# DR_EIB-128_Circle_0_25MM.net
KiCad netlist of a schematic drawn in EAGLE
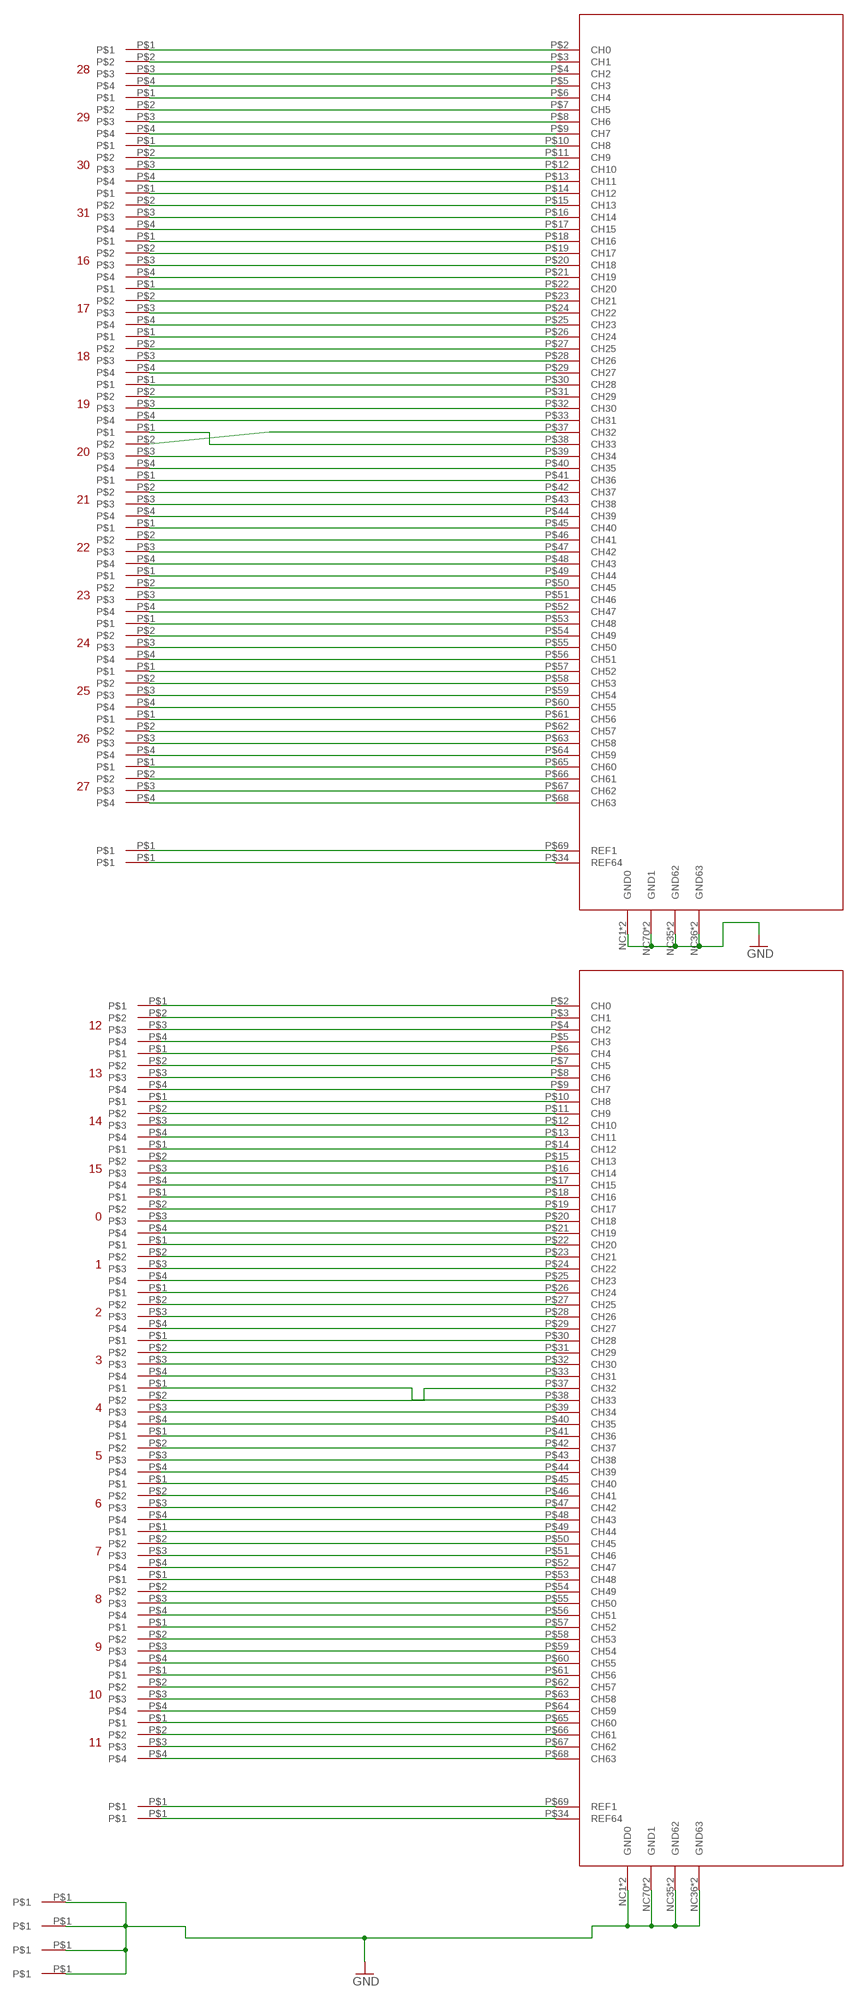
[diagram p0: schematic, sheet 1]

(export (version "E")
  (design (tool "Eeschema 10.0.6"))
  (components
    (comp (ref "0")
      (value "TETRODE_1.5IN_RADIUS0.25MM")
      (footprint "eagle-import:TETRODE_1.5IN_RADIUS_0.25MM")
      (libsource (lib "eagle-import") (part "TETRODE_1.5IN_RADIUS0.25MM"))
    )
    (comp (ref "1")
      (value "TETRODE_1.5IN_RADIUS0.25MM")
      (footprint "eagle-import:TETRODE_1.5IN_RADIUS_0.25MM")
      (libsource (lib "eagle-import") (part "TETRODE_1.5IN_RADIUS0.25MM"))
    )
    (comp (ref "2")
      (value "TETRODE_1.5IN_RADIUS0.25MM")
      (footprint "eagle-import:TETRODE_1.5IN_RADIUS_0.25MM")
      (libsource (lib "eagle-import") (part "TETRODE_1.5IN_RADIUS0.25MM"))
    )
    (comp (ref "3")
      (value "TETRODE_1.5IN_RADIUS0.25MM")
      (footprint "eagle-import:TETRODE_1.5IN_RADIUS_0.25MM")
      (libsource (lib "eagle-import") (part "TETRODE_1.5IN_RADIUS0.25MM"))
    )
    (comp (ref "4")
      (value "TETRODE_1.5IN_RADIUS0.25MM")
      (footprint "eagle-import:TETRODE_1.5IN_RADIUS_0.25MM")
      (libsource (lib "eagle-import") (part "TETRODE_1.5IN_RADIUS0.25MM"))
    )
    (comp (ref "5")
      (value "TETRODE_1.5IN_RADIUS0.25MM")
      (footprint "eagle-import:TETRODE_1.5IN_RADIUS_0.25MM")
      (libsource (lib "eagle-import") (part "TETRODE_1.5IN_RADIUS0.25MM"))
    )
    (comp (ref "6")
      (value "TETRODE_1.5IN_RADIUS0.25MM")
      (footprint "eagle-import:TETRODE_1.5IN_RADIUS_0.25MM")
      (libsource (lib "eagle-import") (part "TETRODE_1.5IN_RADIUS0.25MM"))
    )
    (comp (ref "7")
      (value "TETRODE_1.5IN_RADIUS0.25MM")
      (footprint "eagle-import:TETRODE_1.5IN_RADIUS_0.25MM")
      (libsource (lib "eagle-import") (part "TETRODE_1.5IN_RADIUS0.25MM"))
    )
    (comp (ref "8")
      (value "TETRODE_1.5IN_RADIUS0.25MM")
      (footprint "eagle-import:TETRODE_1.5IN_RADIUS_0.25MM")
      (libsource (lib "eagle-import") (part "TETRODE_1.5IN_RADIUS0.25MM"))
    )
    (comp (ref "9")
      (value "TETRODE_1.5IN_RADIUS0.25MM")
      (footprint "eagle-import:TETRODE_1.5IN_RADIUS_0.25MM")
      (libsource (lib "eagle-import") (part "TETRODE_1.5IN_RADIUS0.25MM"))
    )
    (comp (ref "10")
      (value "TETRODE_1.5IN_RADIUS0.25MM")
      (footprint "eagle-import:TETRODE_1.5IN_RADIUS_0.25MM")
      (libsource (lib "eagle-import") (part "TETRODE_1.5IN_RADIUS0.25MM"))
    )
    (comp (ref "11")
      (value "TETRODE_1.5IN_RADIUS0.25MM")
      (footprint "eagle-import:TETRODE_1.5IN_RADIUS_0.25MM")
      (libsource (lib "eagle-import") (part "TETRODE_1.5IN_RADIUS0.25MM"))
    )
    (comp (ref "12")
      (value "TETRODE_1.5IN_RADIUS0.25MM")
      (footprint "eagle-import:TETRODE_1.5IN_RADIUS_0.25MM")
      (libsource (lib "eagle-import") (part "TETRODE_1.5IN_RADIUS0.25MM"))
    )
    (comp (ref "13")
      (value "TETRODE_1.5IN_RADIUS0.25MM")
      (footprint "eagle-import:TETRODE_1.5IN_RADIUS_0.25MM")
      (libsource (lib "eagle-import") (part "TETRODE_1.5IN_RADIUS0.25MM"))
    )
    (comp (ref "14")
      (value "TETRODE_1.5IN_RADIUS0.25MM")
      (footprint "eagle-import:TETRODE_1.5IN_RADIUS_0.25MM")
      (libsource (lib "eagle-import") (part "TETRODE_1.5IN_RADIUS0.25MM"))
    )
    (comp (ref "15")
      (value "TETRODE_1.5IN_RADIUS0.25MM")
      (footprint "eagle-import:TETRODE_1.5IN_RADIUS_0.25MM")
      (libsource (lib "eagle-import") (part "TETRODE_1.5IN_RADIUS0.25MM"))
    )
    (comp (ref "16")
      (value "TETRODE_1.5IN_RADIUS0.25MM")
      (footprint "eagle-import:TETRODE_1.5IN_RADIUS_0.25MM")
      (libsource (lib "eagle-import") (part "TETRODE_1.5IN_RADIUS0.25MM"))
    )
    (comp (ref "17")
      (value "TETRODE_1.5IN_RADIUS0.25MM")
      (footprint "eagle-import:TETRODE_1.5IN_RADIUS_0.25MM")
      (libsource (lib "eagle-import") (part "TETRODE_1.5IN_RADIUS0.25MM"))
    )
    (comp (ref "18")
      (value "TETRODE_1.5IN_RADIUS0.25MM")
      (footprint "eagle-import:TETRODE_1.5IN_RADIUS_0.25MM")
      (libsource (lib "eagle-import") (part "TETRODE_1.5IN_RADIUS0.25MM"))
    )
    (comp (ref "19")
      (value "TETRODE_1.5IN_RADIUS0.25MM")
      (footprint "eagle-import:TETRODE_1.5IN_RADIUS_0.25MM")
      (libsource (lib "eagle-import") (part "TETRODE_1.5IN_RADIUS0.25MM"))
    )
    (comp (ref "20")
      (value "TETRODE_1.5IN_RADIUS0.25MM")
      (footprint "eagle-import:TETRODE_1.5IN_RADIUS_0.25MM")
      (libsource (lib "eagle-import") (part "TETRODE_1.5IN_RADIUS0.25MM"))
    )
    (comp (ref "21")
      (value "TETRODE_1.5IN_RADIUS0.25MM")
      (footprint "eagle-import:TETRODE_1.5IN_RADIUS_0.25MM")
      (libsource (lib "eagle-import") (part "TETRODE_1.5IN_RADIUS0.25MM"))
    )
    (comp (ref "22")
      (value "TETRODE_1.5IN_RADIUS0.25MM")
      (footprint "eagle-import:TETRODE_1.5IN_RADIUS_0.25MM")
      (libsource (lib "eagle-import") (part "TETRODE_1.5IN_RADIUS0.25MM"))
    )
    (comp (ref "23")
      (value "TETRODE_1.5IN_RADIUS0.25MM")
      (footprint "eagle-import:TETRODE_1.5IN_RADIUS_0.25MM")
      (libsource (lib "eagle-import") (part "TETRODE_1.5IN_RADIUS0.25MM"))
    )
    (comp (ref "24")
      (value "TETRODE_1.5IN_RADIUS0.25MM")
      (footprint "eagle-import:TETRODE_1.5IN_RADIUS_0.25MM")
      (libsource (lib "eagle-import") (part "TETRODE_1.5IN_RADIUS0.25MM"))
    )
    (comp (ref "25")
      (value "TETRODE_1.5IN_RADIUS0.25MM")
      (footprint "eagle-import:TETRODE_1.5IN_RADIUS_0.25MM")
      (libsource (lib "eagle-import") (part "TETRODE_1.5IN_RADIUS0.25MM"))
    )
    (comp (ref "26")
      (value "TETRODE_1.5IN_RADIUS0.25MM")
      (footprint "eagle-import:TETRODE_1.5IN_RADIUS_0.25MM")
      (libsource (lib "eagle-import") (part "TETRODE_1.5IN_RADIUS0.25MM"))
    )
    (comp (ref "27")
      (value "TETRODE_1.5IN_RADIUS0.25MM")
      (footprint "eagle-import:TETRODE_1.5IN_RADIUS_0.25MM")
      (libsource (lib "eagle-import") (part "TETRODE_1.5IN_RADIUS0.25MM"))
    )
    (comp (ref "28")
      (value "TETRODE_1.5IN_RADIUS0.25MM")
      (footprint "eagle-import:TETRODE_1.5IN_RADIUS_0.25MM")
      (libsource (lib "eagle-import") (part "TETRODE_1.5IN_RADIUS0.25MM"))
    )
    (comp (ref "29")
      (value "TETRODE_1.5IN_RADIUS0.25MM")
      (footprint "eagle-import:TETRODE_1.5IN_RADIUS_0.25MM")
      (libsource (lib "eagle-import") (part "TETRODE_1.5IN_RADIUS0.25MM"))
    )
    (comp (ref "30")
      (value "TETRODE_1.5IN_RADIUS0.25MM")
      (footprint "eagle-import:TETRODE_1.5IN_RADIUS_0.25MM")
      (libsource (lib "eagle-import") (part "TETRODE_1.5IN_RADIUS0.25MM"))
    )
    (comp (ref "31")
      (value "TETRODE_1.5IN_RADIUS0.25MM")
      (footprint "eagle-import:TETRODE_1.5IN_RADIUS_0.25MM")
      (libsource (lib "eagle-import") (part "TETRODE_1.5IN_RADIUS0.25MM"))
    )
    (comp (ref "U$1")
      (value "TARRAYSHUTTLEHOLE")
      (footprint "eagle-import:TARRAYSHUTTLEHOLE")
      (libsource (lib "eagle-import") (part "TARRAYSHUTTLEHOLE"))
    )
    (comp (ref "U$2")
      (value "TARRAYSHUTTLEHOLE")
      (footprint "eagle-import:TARRAYSHUTTLEHOLE")
      (libsource (lib "eagle-import") (part "TARRAYSHUTTLEHOLE"))
    )
    (comp (ref "U$4")
      (value "TARRAYSHUTTLEHOLE")
      (footprint "eagle-import:TARRAYSHUTTLEHOLE")
      (libsource (lib "eagle-import") (part "TARRAYSHUTTLEHOLE"))
    )
    (comp (ref "U$5")
      (value "TARRAYSHUTTLEHOLE")
      (footprint "eagle-import:TARRAYSHUTTLEHOLE")
      (libsource (lib "eagle-import") (part "TARRAYSHUTTLEHOLE"))
    )
    (comp (ref "U$6")
      (value "TARRAYSHUTTLEHOLE")
      (footprint "eagle-import:TARRAYSHUTTLEHOLE")
      (libsource (lib "eagle-import") (part "TARRAYSHUTTLEHOLE"))
    )
    (comp (ref "U$7")
      (value "TARRAYSHUTTLEHOLE")
      (footprint "eagle-import:TARRAYSHUTTLEHOLE")
      (libsource (lib "eagle-import") (part "TARRAYSHUTTLEHOLE"))
    )
    (comp (ref "U$8")
      (value "TARRAYSHUTTLEHOLE")
      (footprint "eagle-import:TARRAYSHUTTLEHOLE")
      (libsource (lib "eagle-import") (part "TARRAYSHUTTLEHOLE"))
    )
    (comp (ref "U$9")
      (value "TARRAYSHUTTLEHOLE")
      (footprint "eagle-import:TARRAYSHUTTLEHOLE")
      (libsource (lib "eagle-import") (part "TARRAYSHUTTLEHOLE"))
    )
    (comp (ref "U$10")
      (value "HIROSE-70PIN-HEADER-SEQUENTIAL")
      (footprint "eagle-import:DF40C-70DP-0.4V")
      (libsource (lib "eagle-import") (part "HIROSE-70PIN-HEADER-SEQUENTIAL"))
    )
    (comp (ref "U$11")
      (value "HIROSE-70PIN-HEADER-SEQUENTIAL")
      (footprint "eagle-import:DF40C-70DP-0.4V")
      (libsource (lib "eagle-import") (part "HIROSE-70PIN-HEADER-SEQUENTIAL"))
    )
  )
  (nets
    (net (code "1") (name "GND") (class "Default")
      (node (ref "U$1") (pin "P$1") (pinfunction "P$1_P$1") (pintype "bidirectional"))
      (node (ref "U$10") (pin "NC1") (pinfunction "GND0_NC1") (pintype "power_in"))
      (node (ref "U$10") (pin "NC35") (pinfunction "GND62_NC35") (pintype "power_in"))
      (node (ref "U$10") (pin "NC36") (pinfunction "GND63_NC36") (pintype "power_in"))
      (node (ref "U$10") (pin "NC70") (pinfunction "GND1_NC70") (pintype "power_in"))
      (node (ref "U$10") (pin "P$1") (pinfunction "GND0_P$1") (pintype "power_in"))
      (node (ref "U$10") (pin "P$35") (pinfunction "GND62_P$35") (pintype "power_in"))
      (node (ref "U$10") (pin "P$36") (pinfunction "GND63_P$36") (pintype "power_in"))
      (node (ref "U$10") (pin "P$70") (pinfunction "GND1_P$70") (pintype "power_in"))
      (node (ref "U$11") (pin "NC1") (pinfunction "GND0_NC1") (pintype "power_in"))
      (node (ref "U$11") (pin "NC35") (pinfunction "GND62_NC35") (pintype "power_in"))
      (node (ref "U$11") (pin "NC36") (pinfunction "GND63_NC36") (pintype "power_in"))
      (node (ref "U$11") (pin "NC70") (pinfunction "GND1_NC70") (pintype "power_in"))
      (node (ref "U$11") (pin "P$1") (pinfunction "GND0_P$1") (pintype "power_in"))
      (node (ref "U$11") (pin "P$35") (pinfunction "GND62_P$35") (pintype "power_in"))
      (node (ref "U$11") (pin "P$36") (pinfunction "GND63_P$36") (pintype "power_in"))
      (node (ref "U$11") (pin "P$70") (pinfunction "GND1_P$70") (pintype "power_in"))
      (node (ref "U$2") (pin "P$1") (pinfunction "P$1_P$1") (pintype "bidirectional"))
      (node (ref "U$4") (pin "P$1") (pinfunction "P$1_P$1") (pintype "bidirectional"))
      (node (ref "U$5") (pin "P$1") (pinfunction "P$1_P$1") (pintype "bidirectional"))
    )
    (net (code "2") (name "Net-(U$10-CH0)") (class "Default")
      (node (ref "28") (pin "P$1") (pinfunction "P$1_P$1") (pintype "bidirectional"))
      (node (ref "U$10") (pin "P$2") (pinfunction "CH0_P$2") (pintype "input"))
    )
    (net (code "3") (name "Net-(U$10-CH1)") (class "Default")
      (node (ref "28") (pin "P$2") (pinfunction "P$2_P$2") (pintype "bidirectional"))
      (node (ref "U$10") (pin "P$3") (pinfunction "CH1_P$3") (pintype "input"))
    )
    (net (code "4") (name "Net-(U$10-CH2)") (class "Default")
      (node (ref "28") (pin "P$3") (pinfunction "P$3_P$3") (pintype "bidirectional"))
      (node (ref "U$10") (pin "P$4") (pinfunction "CH2_P$4") (pintype "input"))
    )
    (net (code "5") (name "Net-(U$10-CH3)") (class "Default")
      (node (ref "28") (pin "P$4") (pinfunction "P$4_P$4") (pintype "bidirectional"))
      (node (ref "U$10") (pin "P$5") (pinfunction "CH3_P$5") (pintype "input"))
    )
    (net (code "6") (name "Net-(U$10-CH4)") (class "Default")
      (node (ref "29") (pin "P$1") (pinfunction "P$1_P$1") (pintype "bidirectional"))
      (node (ref "U$10") (pin "P$6") (pinfunction "CH4_P$6") (pintype "input"))
    )
    (net (code "7") (name "Net-(U$10-CH5)") (class "Default")
      (node (ref "29") (pin "P$2") (pinfunction "P$2_P$2") (pintype "bidirectional"))
      (node (ref "U$10") (pin "P$7") (pinfunction "CH5_P$7") (pintype "input"))
    )
    (net (code "8") (name "Net-(U$10-CH6)") (class "Default")
      (node (ref "29") (pin "P$3") (pinfunction "P$3_P$3") (pintype "bidirectional"))
      (node (ref "U$10") (pin "P$8") (pinfunction "CH6_P$8") (pintype "input"))
    )
    (net (code "9") (name "Net-(U$10-CH7)") (class "Default")
      (node (ref "29") (pin "P$4") (pinfunction "P$4_P$4") (pintype "bidirectional"))
      (node (ref "U$10") (pin "P$9") (pinfunction "CH7_P$9") (pintype "input"))
    )
    (net (code "10") (name "Net-(U$10-CH8)") (class "Default")
      (node (ref "30") (pin "P$1") (pinfunction "P$1_P$1") (pintype "bidirectional"))
      (node (ref "U$10") (pin "P$10") (pinfunction "CH8_P$10") (pintype "input"))
    )
    (net (code "11") (name "Net-(U$10-CH9)") (class "Default")
      (node (ref "30") (pin "P$2") (pinfunction "P$2_P$2") (pintype "bidirectional"))
      (node (ref "U$10") (pin "P$11") (pinfunction "CH9_P$11") (pintype "input"))
    )
    (net (code "12") (name "Net-(U$10-CH10)") (class "Default")
      (node (ref "30") (pin "P$3") (pinfunction "P$3_P$3") (pintype "bidirectional"))
      (node (ref "U$10") (pin "P$12") (pinfunction "CH10_P$12") (pintype "input"))
    )
    (net (code "13") (name "Net-(U$10-CH11)") (class "Default")
      (node (ref "30") (pin "P$4") (pinfunction "P$4_P$4") (pintype "bidirectional"))
      (node (ref "U$10") (pin "P$13") (pinfunction "CH11_P$13") (pintype "input"))
    )
    (net (code "14") (name "Net-(U$10-CH12)") (class "Default")
      (node (ref "31") (pin "P$1") (pinfunction "P$1_P$1") (pintype "bidirectional"))
      (node (ref "U$10") (pin "P$14") (pinfunction "CH12_P$14") (pintype "input"))
    )
    (net (code "15") (name "Net-(U$10-CH13)") (class "Default")
      (node (ref "31") (pin "P$2") (pinfunction "P$2_P$2") (pintype "bidirectional"))
      (node (ref "U$10") (pin "P$15") (pinfunction "CH13_P$15") (pintype "input"))
    )
    (net (code "16") (name "Net-(U$10-CH14)") (class "Default")
      (node (ref "31") (pin "P$3") (pinfunction "P$3_P$3") (pintype "bidirectional"))
      (node (ref "U$10") (pin "P$16") (pinfunction "CH14_P$16") (pintype "input"))
    )
    (net (code "17") (name "Net-(U$10-CH15)") (class "Default")
      (node (ref "31") (pin "P$4") (pinfunction "P$4_P$4") (pintype "bidirectional"))
      (node (ref "U$10") (pin "P$17") (pinfunction "CH15_P$17") (pintype "input"))
    )
    (net (code "18") (name "Net-(U$10-CH16)") (class "Default")
      (node (ref "16") (pin "P$1") (pinfunction "P$1_P$1") (pintype "bidirectional"))
      (node (ref "U$10") (pin "P$18") (pinfunction "CH16_P$18") (pintype "input"))
    )
    (net (code "19") (name "Net-(U$10-CH17)") (class "Default")
      (node (ref "16") (pin "P$2") (pinfunction "P$2_P$2") (pintype "bidirectional"))
      (node (ref "U$10") (pin "P$19") (pinfunction "CH17_P$19") (pintype "input"))
    )
    (net (code "20") (name "Net-(U$10-CH18)") (class "Default")
      (node (ref "16") (pin "P$3") (pinfunction "P$3_P$3") (pintype "bidirectional"))
      (node (ref "U$10") (pin "P$20") (pinfunction "CH18_P$20") (pintype "input"))
    )
    (net (code "21") (name "Net-(U$10-CH19)") (class "Default")
      (node (ref "16") (pin "P$4") (pinfunction "P$4_P$4") (pintype "bidirectional"))
      (node (ref "U$10") (pin "P$21") (pinfunction "CH19_P$21") (pintype "input"))
    )
    (net (code "22") (name "Net-(U$10-CH20)") (class "Default")
      (node (ref "17") (pin "P$1") (pinfunction "P$1_P$1") (pintype "bidirectional"))
      (node (ref "U$10") (pin "P$22") (pinfunction "CH20_P$22") (pintype "input"))
    )
    (net (code "23") (name "Net-(U$10-CH21)") (class "Default")
      (node (ref "17") (pin "P$2") (pinfunction "P$2_P$2") (pintype "bidirectional"))
      (node (ref "U$10") (pin "P$23") (pinfunction "CH21_P$23") (pintype "input"))
    )
    (net (code "24") (name "Net-(U$10-CH22)") (class "Default")
      (node (ref "17") (pin "P$3") (pinfunction "P$3_P$3") (pintype "bidirectional"))
      (node (ref "U$10") (pin "P$24") (pinfunction "CH22_P$24") (pintype "input"))
    )
    (net (code "25") (name "Net-(U$10-CH23)") (class "Default")
      (node (ref "17") (pin "P$4") (pinfunction "P$4_P$4") (pintype "bidirectional"))
      (node (ref "U$10") (pin "P$25") (pinfunction "CH23_P$25") (pintype "input"))
    )
    (net (code "26") (name "Net-(U$10-CH24)") (class "Default")
      (node (ref "18") (pin "P$1") (pinfunction "P$1_P$1") (pintype "bidirectional"))
      (node (ref "U$10") (pin "P$26") (pinfunction "CH24_P$26") (pintype "input"))
    )
    (net (code "27") (name "Net-(U$10-CH25)") (class "Default")
      (node (ref "18") (pin "P$2") (pinfunction "P$2_P$2") (pintype "bidirectional"))
      (node (ref "U$10") (pin "P$27") (pinfunction "CH25_P$27") (pintype "input"))
    )
    (net (code "28") (name "Net-(U$10-CH26)") (class "Default")
      (node (ref "18") (pin "P$3") (pinfunction "P$3_P$3") (pintype "bidirectional"))
      (node (ref "U$10") (pin "P$28") (pinfunction "CH26_P$28") (pintype "input"))
    )
    (net (code "29") (name "Net-(U$10-CH27)") (class "Default")
      (node (ref "18") (pin "P$4") (pinfunction "P$4_P$4") (pintype "bidirectional"))
      (node (ref "U$10") (pin "P$29") (pinfunction "CH27_P$29") (pintype "input"))
    )
    (net (code "30") (name "Net-(U$10-CH28)") (class "Default")
      (node (ref "19") (pin "P$1") (pinfunction "P$1_P$1") (pintype "bidirectional"))
      (node (ref "U$10") (pin "P$30") (pinfunction "CH28_P$30") (pintype "input"))
    )
    (net (code "31") (name "Net-(U$10-CH29)") (class "Default")
      (node (ref "19") (pin "P$2") (pinfunction "P$2_P$2") (pintype "bidirectional"))
      (node (ref "U$10") (pin "P$31") (pinfunction "CH29_P$31") (pintype "input"))
    )
    (net (code "32") (name "Net-(U$10-CH30)") (class "Default")
      (node (ref "19") (pin "P$3") (pinfunction "P$3_P$3") (pintype "bidirectional"))
      (node (ref "U$10") (pin "P$32") (pinfunction "CH30_P$32") (pintype "input"))
    )
    (net (code "33") (name "Net-(U$10-CH31)") (class "Default")
      (node (ref "19") (pin "P$4") (pinfunction "P$4_P$4") (pintype "bidirectional"))
      (node (ref "U$10") (pin "P$33") (pinfunction "CH31_P$33") (pintype "input"))
    )
    (net (code "34") (name "Net-(U$10-CH32)") (class "Default")
      (node (ref "20") (pin "P$2") (pinfunction "P$2_P$2") (pintype "bidirectional"))
      (node (ref "U$10") (pin "P$37") (pinfunction "CH32_P$37") (pintype "input"))
    )
    (net (code "35") (name "Net-(U$10-CH33)") (class "Default")
      (node (ref "20") (pin "P$1") (pinfunction "P$1_P$1") (pintype "bidirectional"))
      (node (ref "U$10") (pin "P$38") (pinfunction "CH33_P$38") (pintype "input"))
    )
    (net (code "36") (name "Net-(U$10-CH34)") (class "Default")
      (node (ref "20") (pin "P$3") (pinfunction "P$3_P$3") (pintype "bidirectional"))
      (node (ref "U$10") (pin "P$39") (pinfunction "CH34_P$39") (pintype "input"))
    )
    (net (code "37") (name "Net-(U$10-CH35)") (class "Default")
      (node (ref "20") (pin "P$4") (pinfunction "P$4_P$4") (pintype "bidirectional"))
      (node (ref "U$10") (pin "P$40") (pinfunction "CH35_P$40") (pintype "input"))
    )
    (net (code "38") (name "Net-(U$10-CH36)") (class "Default")
      (node (ref "21") (pin "P$1") (pinfunction "P$1_P$1") (pintype "bidirectional"))
      (node (ref "U$10") (pin "P$41") (pinfunction "CH36_P$41") (pintype "input"))
    )
    (net (code "39") (name "Net-(U$10-CH37)") (class "Default")
      (node (ref "21") (pin "P$2") (pinfunction "P$2_P$2") (pintype "bidirectional"))
      (node (ref "U$10") (pin "P$42") (pinfunction "CH37_P$42") (pintype "input"))
    )
    (net (code "40") (name "Net-(U$10-CH38)") (class "Default")
      (node (ref "21") (pin "P$3") (pinfunction "P$3_P$3") (pintype "bidirectional"))
      (node (ref "U$10") (pin "P$43") (pinfunction "CH38_P$43") (pintype "input"))
    )
    (net (code "41") (name "Net-(U$10-CH39)") (class "Default")
      (node (ref "21") (pin "P$4") (pinfunction "P$4_P$4") (pintype "bidirectional"))
      (node (ref "U$10") (pin "P$44") (pinfunction "CH39_P$44") (pintype "input"))
    )
    (net (code "42") (name "Net-(U$10-CH40)") (class "Default")
      (node (ref "22") (pin "P$1") (pinfunction "P$1_P$1") (pintype "bidirectional"))
      (node (ref "U$10") (pin "P$45") (pinfunction "CH40_P$45") (pintype "input"))
    )
    (net (code "43") (name "Net-(U$10-CH41)") (class "Default")
      (node (ref "22") (pin "P$2") (pinfunction "P$2_P$2") (pintype "bidirectional"))
      (node (ref "U$10") (pin "P$46") (pinfunction "CH41_P$46") (pintype "input"))
    )
    (net (code "44") (name "Net-(U$10-CH42)") (class "Default")
      (node (ref "22") (pin "P$3") (pinfunction "P$3_P$3") (pintype "bidirectional"))
      (node (ref "U$10") (pin "P$47") (pinfunction "CH42_P$47") (pintype "input"))
    )
    (net (code "45") (name "Net-(U$10-CH43)") (class "Default")
      (node (ref "22") (pin "P$4") (pinfunction "P$4_P$4") (pintype "bidirectional"))
      (node (ref "U$10") (pin "P$48") (pinfunction "CH43_P$48") (pintype "input"))
    )
    (net (code "46") (name "Net-(U$10-CH44)") (class "Default")
      (node (ref "23") (pin "P$1") (pinfunction "P$1_P$1") (pintype "bidirectional"))
      (node (ref "U$10") (pin "P$49") (pinfunction "CH44_P$49") (pintype "input"))
    )
    (net (code "47") (name "Net-(U$10-CH45)") (class "Default")
      (node (ref "23") (pin "P$2") (pinfunction "P$2_P$2") (pintype "bidirectional"))
      (node (ref "U$10") (pin "P$50") (pinfunction "CH45_P$50") (pintype "input"))
    )
    (net (code "48") (name "Net-(U$10-CH46)") (class "Default")
      (node (ref "23") (pin "P$3") (pinfunction "P$3_P$3") (pintype "bidirectional"))
      (node (ref "U$10") (pin "P$51") (pinfunction "CH46_P$51") (pintype "input"))
    )
    (net (code "49") (name "Net-(U$10-CH47)") (class "Default")
      (node (ref "23") (pin "P$4") (pinfunction "P$4_P$4") (pintype "bidirectional"))
      (node (ref "U$10") (pin "P$52") (pinfunction "CH47_P$52") (pintype "input"))
    )
    (net (code "50") (name "Net-(U$10-CH48)") (class "Default")
      (node (ref "24") (pin "P$1") (pinfunction "P$1_P$1") (pintype "bidirectional"))
      (node (ref "U$10") (pin "P$53") (pinfunction "CH48_P$53") (pintype "input"))
    )
    (net (code "51") (name "Net-(U$10-CH49)") (class "Default")
      (node (ref "24") (pin "P$2") (pinfunction "P$2_P$2") (pintype "bidirectional"))
      (node (ref "U$10") (pin "P$54") (pinfunction "CH49_P$54") (pintype "input"))
    )
    (net (code "52") (name "Net-(U$10-CH50)") (class "Default")
      (node (ref "24") (pin "P$3") (pinfunction "P$3_P$3") (pintype "bidirectional"))
      (node (ref "U$10") (pin "P$55") (pinfunction "CH50_P$55") (pintype "input"))
    )
    (net (code "53") (name "Net-(U$10-CH51)") (class "Default")
      (node (ref "24") (pin "P$4") (pinfunction "P$4_P$4") (pintype "bidirectional"))
      (node (ref "U$10") (pin "P$56") (pinfunction "CH51_P$56") (pintype "input"))
    )
    (net (code "54") (name "Net-(U$10-CH52)") (class "Default")
      (node (ref "25") (pin "P$1") (pinfunction "P$1_P$1") (pintype "bidirectional"))
      (node (ref "U$10") (pin "P$57") (pinfunction "CH52_P$57") (pintype "input"))
    )
    (net (code "55") (name "Net-(U$10-CH53)") (class "Default")
      (node (ref "25") (pin "P$2") (pinfunction "P$2_P$2") (pintype "bidirectional"))
      (node (ref "U$10") (pin "P$58") (pinfunction "CH53_P$58") (pintype "input"))
    )
    (net (code "56") (name "Net-(U$10-CH54)") (class "Default")
      (node (ref "25") (pin "P$3") (pinfunction "P$3_P$3") (pintype "bidirectional"))
      (node (ref "U$10") (pin "P$59") (pinfunction "CH54_P$59") (pintype "input"))
    )
    (net (code "57") (name "Net-(U$10-CH55)") (class "Default")
      (node (ref "25") (pin "P$4") (pinfunction "P$4_P$4") (pintype "bidirectional"))
      (node (ref "U$10") (pin "P$60") (pinfunction "CH55_P$60") (pintype "input"))
    )
    (net (code "58") (name "Net-(U$10-CH56)") (class "Default")
      (node (ref "26") (pin "P$1") (pinfunction "P$1_P$1") (pintype "bidirectional"))
      (node (ref "U$10") (pin "P$61") (pinfunction "CH56_P$61") (pintype "input"))
    )
    (net (code "59") (name "Net-(U$10-CH57)") (class "Default")
      (node (ref "26") (pin "P$2") (pinfunction "P$2_P$2") (pintype "bidirectional"))
      (node (ref "U$10") (pin "P$62") (pinfunction "CH57_P$62") (pintype "input"))
    )
    (net (code "60") (name "Net-(U$10-CH58)") (class "Default")
      (node (ref "26") (pin "P$3") (pinfunction "P$3_P$3") (pintype "bidirectional"))
      (node (ref "U$10") (pin "P$63") (pinfunction "CH58_P$63") (pintype "input"))
    )
    (net (code "61") (name "Net-(U$10-CH59)") (class "Default")
      (node (ref "26") (pin "P$4") (pinfunction "P$4_P$4") (pintype "bidirectional"))
      (node (ref "U$10") (pin "P$64") (pinfunction "CH59_P$64") (pintype "input"))
    )
    (net (code "62") (name "Net-(U$10-CH60)") (class "Default")
      (node (ref "27") (pin "P$1") (pinfunction "P$1_P$1") (pintype "bidirectional"))
      (node (ref "U$10") (pin "P$65") (pinfunction "CH60_P$65") (pintype "input"))
    )
    (net (code "63") (name "Net-(U$10-CH61)") (class "Default")
      (node (ref "27") (pin "P$2") (pinfunction "P$2_P$2") (pintype "bidirectional"))
      (node (ref "U$10") (pin "P$66") (pinfunction "CH61_P$66") (pintype "input"))
    )
    (net (code "64") (name "Net-(U$10-CH62)") (class "Default")
      (node (ref "27") (pin "P$3") (pinfunction "P$3_P$3") (pintype "bidirectional"))
      (node (ref "U$10") (pin "P$67") (pinfunction "CH62_P$67") (pintype "input"))
    )
    (net (code "65") (name "Net-(U$10-CH63)") (class "Default")
      (node (ref "27") (pin "P$4") (pinfunction "P$4_P$4") (pintype "bidirectional"))
      (node (ref "U$10") (pin "P$68") (pinfunction "CH63_P$68") (pintype "input"))
    )
    (net (code "66") (name "Net-(U$10-REF1)") (class "Default")
      (node (ref "U$10") (pin "P$69") (pinfunction "REF1_P$69") (pintype "input"))
      (node (ref "U$7") (pin "P$1") (pinfunction "P$1_P$1") (pintype "bidirectional"))
    )
    (net (code "67") (name "Net-(U$10-REF64)") (class "Default")
      (node (ref "U$10") (pin "P$34") (pinfunction "REF64_P$34") (pintype "input"))
      (node (ref "U$6") (pin "P$1") (pinfunction "P$1_P$1") (pintype "bidirectional"))
    )
    (net (code "68") (name "Net-(U$11-CH0)") (class "Default")
      (node (ref "12") (pin "P$1") (pinfunction "P$1_P$1") (pintype "bidirectional"))
      (node (ref "U$11") (pin "P$2") (pinfunction "CH0_P$2") (pintype "input"))
    )
    (net (code "69") (name "Net-(U$11-CH1)") (class "Default")
      (node (ref "12") (pin "P$2") (pinfunction "P$2_P$2") (pintype "bidirectional"))
      (node (ref "U$11") (pin "P$3") (pinfunction "CH1_P$3") (pintype "input"))
    )
    (net (code "70") (name "Net-(U$11-CH2)") (class "Default")
      (node (ref "12") (pin "P$3") (pinfunction "P$3_P$3") (pintype "bidirectional"))
      (node (ref "U$11") (pin "P$4") (pinfunction "CH2_P$4") (pintype "input"))
    )
    (net (code "71") (name "Net-(U$11-CH3)") (class "Default")
      (node (ref "12") (pin "P$4") (pinfunction "P$4_P$4") (pintype "bidirectional"))
      (node (ref "U$11") (pin "P$5") (pinfunction "CH3_P$5") (pintype "input"))
    )
    (net (code "72") (name "Net-(U$11-CH4)") (class "Default")
      (node (ref "13") (pin "P$1") (pinfunction "P$1_P$1") (pintype "bidirectional"))
      (node (ref "U$11") (pin "P$6") (pinfunction "CH4_P$6") (pintype "input"))
    )
    (net (code "73") (name "Net-(U$11-CH5)") (class "Default")
      (node (ref "13") (pin "P$2") (pinfunction "P$2_P$2") (pintype "bidirectional"))
      (node (ref "U$11") (pin "P$7") (pinfunction "CH5_P$7") (pintype "input"))
    )
    (net (code "74") (name "Net-(U$11-CH6)") (class "Default")
      (node (ref "13") (pin "P$3") (pinfunction "P$3_P$3") (pintype "bidirectional"))
      (node (ref "U$11") (pin "P$8") (pinfunction "CH6_P$8") (pintype "input"))
    )
    (net (code "75") (name "Net-(U$11-CH7)") (class "Default")
      (node (ref "13") (pin "P$4") (pinfunction "P$4_P$4") (pintype "bidirectional"))
      (node (ref "U$11") (pin "P$9") (pinfunction "CH7_P$9") (pintype "input"))
    )
    (net (code "76") (name "Net-(U$11-CH8)") (class "Default")
      (node (ref "14") (pin "P$1") (pinfunction "P$1_P$1") (pintype "bidirectional"))
      (node (ref "U$11") (pin "P$10") (pinfunction "CH8_P$10") (pintype "input"))
    )
    (net (code "77") (name "Net-(U$11-CH9)") (class "Default")
      (node (ref "14") (pin "P$2") (pinfunction "P$2_P$2") (pintype "bidirectional"))
      (node (ref "U$11") (pin "P$11") (pinfunction "CH9_P$11") (pintype "input"))
    )
    (net (code "78") (name "Net-(U$11-CH10)") (class "Default")
      (node (ref "14") (pin "P$3") (pinfunction "P$3_P$3") (pintype "bidirectional"))
      (node (ref "U$11") (pin "P$12") (pinfunction "CH10_P$12") (pintype "input"))
    )
    (net (code "79") (name "Net-(U$11-CH11)") (class "Default")
      (node (ref "14") (pin "P$4") (pinfunction "P$4_P$4") (pintype "bidirectional"))
      (node (ref "U$11") (pin "P$13") (pinfunction "CH11_P$13") (pintype "input"))
    )
    (net (code "80") (name "Net-(U$11-CH12)") (class "Default")
      (node (ref "15") (pin "P$1") (pinfunction "P$1_P$1") (pintype "bidirectional"))
      (node (ref "U$11") (pin "P$14") (pinfunction "CH12_P$14") (pintype "input"))
    )
    (net (code "81") (name "Net-(U$11-CH13)") (class "Default")
      (node (ref "15") (pin "P$2") (pinfunction "P$2_P$2") (pintype "bidirectional"))
      (node (ref "U$11") (pin "P$15") (pinfunction "CH13_P$15") (pintype "input"))
    )
    (net (code "82") (name "Net-(U$11-CH14)") (class "Default")
      (node (ref "15") (pin "P$3") (pinfunction "P$3_P$3") (pintype "bidirectional"))
      (node (ref "U$11") (pin "P$16") (pinfunction "CH14_P$16") (pintype "input"))
    )
    (net (code "83") (name "Net-(U$11-CH15)") (class "Default")
      (node (ref "15") (pin "P$4") (pinfunction "P$4_P$4") (pintype "bidirectional"))
      (node (ref "U$11") (pin "P$17") (pinfunction "CH15_P$17") (pintype "input"))
    )
    (net (code "84") (name "Net-(U$11-CH16)") (class "Default")
      (node (ref "0") (pin "P$1") (pinfunction "P$1_P$1") (pintype "bidirectional"))
      (node (ref "U$11") (pin "P$18") (pinfunction "CH16_P$18") (pintype "input"))
    )
    (net (code "85") (name "Net-(U$11-CH17)") (class "Default")
      (node (ref "0") (pin "P$2") (pinfunction "P$2_P$2") (pintype "bidirectional"))
      (node (ref "U$11") (pin "P$19") (pinfunction "CH17_P$19") (pintype "input"))
    )
    (net (code "86") (name "Net-(U$11-CH18)") (class "Default")
      (node (ref "0") (pin "P$3") (pinfunction "P$3_P$3") (pintype "bidirectional"))
      (node (ref "U$11") (pin "P$20") (pinfunction "CH18_P$20") (pintype "input"))
    )
    (net (code "87") (name "Net-(U$11-CH19)") (class "Default")
      (node (ref "0") (pin "P$4") (pinfunction "P$4_P$4") (pintype "bidirectional"))
      (node (ref "U$11") (pin "P$21") (pinfunction "CH19_P$21") (pintype "input"))
    )
    (net (code "88") (name "Net-(U$11-CH20)") (class "Default")
      (node (ref "1") (pin "P$1") (pinfunction "P$1_P$1") (pintype "bidirectional"))
      (node (ref "U$11") (pin "P$22") (pinfunction "CH20_P$22") (pintype "input"))
    )
    (net (code "89") (name "Net-(U$11-CH21)") (class "Default")
      (node (ref "1") (pin "P$2") (pinfunction "P$2_P$2") (pintype "bidirectional"))
      (node (ref "U$11") (pin "P$23") (pinfunction "CH21_P$23") (pintype "input"))
    )
    (net (code "90") (name "Net-(U$11-CH22)") (class "Default")
      (node (ref "1") (pin "P$3") (pinfunction "P$3_P$3") (pintype "bidirectional"))
      (node (ref "U$11") (pin "P$24") (pinfunction "CH22_P$24") (pintype "input"))
    )
    (net (code "91") (name "Net-(U$11-CH23)") (class "Default")
      (node (ref "1") (pin "P$4") (pinfunction "P$4_P$4") (pintype "bidirectional"))
      (node (ref "U$11") (pin "P$25") (pinfunction "CH23_P$25") (pintype "input"))
    )
    (net (code "92") (name "Net-(U$11-CH24)") (class "Default")
      (node (ref "2") (pin "P$1") (pinfunction "P$1_P$1") (pintype "bidirectional"))
      (node (ref "U$11") (pin "P$26") (pinfunction "CH24_P$26") (pintype "input"))
    )
    (net (code "93") (name "Net-(U$11-CH25)") (class "Default")
      (node (ref "2") (pin "P$2") (pinfunction "P$2_P$2") (pintype "bidirectional"))
      (node (ref "U$11") (pin "P$27") (pinfunction "CH25_P$27") (pintype "input"))
    )
    (net (code "94") (name "Net-(U$11-CH26)") (class "Default")
      (node (ref "2") (pin "P$3") (pinfunction "P$3_P$3") (pintype "bidirectional"))
      (node (ref "U$11") (pin "P$28") (pinfunction "CH26_P$28") (pintype "input"))
    )
    (net (code "95") (name "Net-(U$11-CH27)") (class "Default")
      (node (ref "2") (pin "P$4") (pinfunction "P$4_P$4") (pintype "bidirectional"))
      (node (ref "U$11") (pin "P$29") (pinfunction "CH27_P$29") (pintype "input"))
    )
    (net (code "96") (name "Net-(U$11-CH28)") (class "Default")
      (node (ref "3") (pin "P$1") (pinfunction "P$1_P$1") (pintype "bidirectional"))
      (node (ref "U$11") (pin "P$30") (pinfunction "CH28_P$30") (pintype "input"))
    )
    (net (code "97") (name "Net-(U$11-CH29)") (class "Default")
      (node (ref "3") (pin "P$2") (pinfunction "P$2_P$2") (pintype "bidirectional"))
      (node (ref "U$11") (pin "P$31") (pinfunction "CH29_P$31") (pintype "input"))
    )
    (net (code "98") (name "Net-(U$11-CH30)") (class "Default")
      (node (ref "3") (pin "P$3") (pinfunction "P$3_P$3") (pintype "bidirectional"))
      (node (ref "U$11") (pin "P$32") (pinfunction "CH30_P$32") (pintype "input"))
    )
    (net (code "99") (name "Net-(U$11-CH31)") (class "Default")
      (node (ref "3") (pin "P$4") (pinfunction "P$4_P$4") (pintype "bidirectional"))
      (node (ref "U$11") (pin "P$33") (pinfunction "CH31_P$33") (pintype "input"))
    )
    (net (code "100") (name "Net-(U$11-CH32)") (class "Default")
      (node (ref "4") (pin "P$2") (pinfunction "P$2_P$2") (pintype "bidirectional"))
      (node (ref "U$11") (pin "P$37") (pinfunction "CH32_P$37") (pintype "input"))
    )
    (net (code "101") (name "Net-(U$11-CH33)") (class "Default")
      (node (ref "4") (pin "P$1") (pinfunction "P$1_P$1") (pintype "bidirectional"))
      (node (ref "U$11") (pin "P$38") (pinfunction "CH33_P$38") (pintype "input"))
    )
    (net (code "102") (name "Net-(U$11-CH34)") (class "Default")
      (node (ref "4") (pin "P$3") (pinfunction "P$3_P$3") (pintype "bidirectional"))
      (node (ref "U$11") (pin "P$39") (pinfunction "CH34_P$39") (pintype "input"))
    )
    (net (code "103") (name "Net-(U$11-CH35)") (class "Default")
      (node (ref "4") (pin "P$4") (pinfunction "P$4_P$4") (pintype "bidirectional"))
      (node (ref "U$11") (pin "P$40") (pinfunction "CH35_P$40") (pintype "input"))
    )
    (net (code "104") (name "Net-(U$11-CH36)") (class "Default")
      (node (ref "5") (pin "P$1") (pinfunction "P$1_P$1") (pintype "bidirectional"))
      (node (ref "U$11") (pin "P$41") (pinfunction "CH36_P$41") (pintype "input"))
    )
    (net (code "105") (name "Net-(U$11-CH37)") (class "Default")
      (node (ref "5") (pin "P$2") (pinfunction "P$2_P$2") (pintype "bidirectional"))
      (node (ref "U$11") (pin "P$42") (pinfunction "CH37_P$42") (pintype "input"))
    )
    (net (code "106") (name "Net-(U$11-CH38)") (class "Default")
      (node (ref "5") (pin "P$3") (pinfunction "P$3_P$3") (pintype "bidirectional"))
      (node (ref "U$11") (pin "P$43") (pinfunction "CH38_P$43") (pintype "input"))
    )
    (net (code "107") (name "Net-(U$11-CH39)") (class "Default")
      (node (ref "5") (pin "P$4") (pinfunction "P$4_P$4") (pintype "bidirectional"))
      (node (ref "U$11") (pin "P$44") (pinfunction "CH39_P$44") (pintype "input"))
    )
    (net (code "108") (name "Net-(U$11-CH40)") (class "Default")
      (node (ref "6") (pin "P$1") (pinfunction "P$1_P$1") (pintype "bidirectional"))
      (node (ref "U$11") (pin "P$45") (pinfunction "CH40_P$45") (pintype "input"))
    )
    (net (code "109") (name "Net-(U$11-CH41)") (class "Default")
      (node (ref "6") (pin "P$2") (pinfunction "P$2_P$2") (pintype "bidirectional"))
      (node (ref "U$11") (pin "P$46") (pinfunction "CH41_P$46") (pintype "input"))
    )
    (net (code "110") (name "Net-(U$11-CH42)") (class "Default")
      (node (ref "6") (pin "P$3") (pinfunction "P$3_P$3") (pintype "bidirectional"))
      (node (ref "U$11") (pin "P$47") (pinfunction "CH42_P$47") (pintype "input"))
    )
    (net (code "111") (name "Net-(U$11-CH43)") (class "Default")
      (node (ref "6") (pin "P$4") (pinfunction "P$4_P$4") (pintype "bidirectional"))
      (node (ref "U$11") (pin "P$48") (pinfunction "CH43_P$48") (pintype "input"))
    )
    (net (code "112") (name "Net-(U$11-CH44)") (class "Default")
      (node (ref "7") (pin "P$1") (pinfunction "P$1_P$1") (pintype "bidirectional"))
      (node (ref "U$11") (pin "P$49") (pinfunction "CH44_P$49") (pintype "input"))
    )
    (net (code "113") (name "Net-(U$11-CH45)") (class "Default")
      (node (ref "7") (pin "P$2") (pinfunction "P$2_P$2") (pintype "bidirectional"))
      (node (ref "U$11") (pin "P$50") (pinfunction "CH45_P$50") (pintype "input"))
    )
    (net (code "114") (name "Net-(U$11-CH46)") (class "Default")
      (node (ref "7") (pin "P$3") (pinfunction "P$3_P$3") (pintype "bidirectional"))
      (node (ref "U$11") (pin "P$51") (pinfunction "CH46_P$51") (pintype "input"))
    )
    (net (code "115") (name "Net-(U$11-CH47)") (class "Default")
      (node (ref "7") (pin "P$4") (pinfunction "P$4_P$4") (pintype "bidirectional"))
      (node (ref "U$11") (pin "P$52") (pinfunction "CH47_P$52") (pintype "input"))
    )
    (net (code "116") (name "Net-(U$11-CH48)") (class "Default")
      (node (ref "8") (pin "P$1") (pinfunction "P$1_P$1") (pintype "bidirectional"))
      (node (ref "U$11") (pin "P$53") (pinfunction "CH48_P$53") (pintype "input"))
    )
    (net (code "117") (name "Net-(U$11-CH49)") (class "Default")
      (node (ref "8") (pin "P$2") (pinfunction "P$2_P$2") (pintype "bidirectional"))
      (node (ref "U$11") (pin "P$54") (pinfunction "CH49_P$54") (pintype "input"))
    )
    (net (code "118") (name "Net-(U$11-CH50)") (class "Default")
      (node (ref "8") (pin "P$3") (pinfunction "P$3_P$3") (pintype "bidirectional"))
      (node (ref "U$11") (pin "P$55") (pinfunction "CH50_P$55") (pintype "input"))
    )
    (net (code "119") (name "Net-(U$11-CH51)") (class "Default")
      (node (ref "8") (pin "P$4") (pinfunction "P$4_P$4") (pintype "bidirectional"))
      (node (ref "U$11") (pin "P$56") (pinfunction "CH51_P$56") (pintype "input"))
    )
    (net (code "120") (name "Net-(U$11-CH52)") (class "Default")
      (node (ref "9") (pin "P$1") (pinfunction "P$1_P$1") (pintype "bidirectional"))
      (node (ref "U$11") (pin "P$57") (pinfunction "CH52_P$57") (pintype "input"))
    )
    (net (code "121") (name "Net-(U$11-CH53)") (class "Default")
      (node (ref "9") (pin "P$2") (pinfunction "P$2_P$2") (pintype "bidirectional"))
      (node (ref "U$11") (pin "P$58") (pinfunction "CH53_P$58") (pintype "input"))
    )
    (net (code "122") (name "Net-(U$11-CH54)") (class "Default")
      (node (ref "9") (pin "P$3") (pinfunction "P$3_P$3") (pintype "bidirectional"))
      (node (ref "U$11") (pin "P$59") (pinfunction "CH54_P$59") (pintype "input"))
    )
    (net (code "123") (name "Net-(U$11-CH55)") (class "Default")
      (node (ref "9") (pin "P$4") (pinfunction "P$4_P$4") (pintype "bidirectional"))
      (node (ref "U$11") (pin "P$60") (pinfunction "CH55_P$60") (pintype "input"))
    )
    (net (code "124") (name "Net-(U$11-CH56)") (class "Default")
      (node (ref "10") (pin "P$1") (pinfunction "P$1_P$1") (pintype "bidirectional"))
      (node (ref "U$11") (pin "P$61") (pinfunction "CH56_P$61") (pintype "input"))
    )
    (net (code "125") (name "Net-(U$11-CH57)") (class "Default")
      (node (ref "10") (pin "P$2") (pinfunction "P$2_P$2") (pintype "bidirectional"))
      (node (ref "U$11") (pin "P$62") (pinfunction "CH57_P$62") (pintype "input"))
    )
    (net (code "126") (name "Net-(U$11-CH58)") (class "Default")
      (node (ref "10") (pin "P$3") (pinfunction "P$3_P$3") (pintype "bidirectional"))
      (node (ref "U$11") (pin "P$63") (pinfunction "CH58_P$63") (pintype "input"))
    )
    (net (code "127") (name "Net-(U$11-CH59)") (class "Default")
      (node (ref "10") (pin "P$4") (pinfunction "P$4_P$4") (pintype "bidirectional"))
      (node (ref "U$11") (pin "P$64") (pinfunction "CH59_P$64") (pintype "input"))
    )
    (net (code "128") (name "Net-(U$11-CH60)") (class "Default")
      (node (ref "11") (pin "P$1") (pinfunction "P$1_P$1") (pintype "bidirectional"))
      (node (ref "U$11") (pin "P$65") (pinfunction "CH60_P$65") (pintype "input"))
    )
    (net (code "129") (name "Net-(U$11-CH61)") (class "Default")
      (node (ref "11") (pin "P$2") (pinfunction "P$2_P$2") (pintype "bidirectional"))
      (node (ref "U$11") (pin "P$66") (pinfunction "CH61_P$66") (pintype "input"))
    )
    (net (code "130") (name "Net-(U$11-CH62)") (class "Default")
      (node (ref "11") (pin "P$3") (pinfunction "P$3_P$3") (pintype "bidirectional"))
      (node (ref "U$11") (pin "P$67") (pinfunction "CH62_P$67") (pintype "input"))
    )
    (net (code "131") (name "Net-(U$11-CH63)") (class "Default")
      (node (ref "11") (pin "P$4") (pinfunction "P$4_P$4") (pintype "bidirectional"))
      (node (ref "U$11") (pin "P$68") (pinfunction "CH63_P$68") (pintype "input"))
    )
    (net (code "132") (name "Net-(U$11-REF1)") (class "Default")
      (node (ref "U$11") (pin "P$69") (pinfunction "REF1_P$69") (pintype "input"))
      (node (ref "U$9") (pin "P$1") (pinfunction "P$1_P$1") (pintype "bidirectional"))
    )
    (net (code "133") (name "Net-(U$11-REF64)") (class "Default")
      (node (ref "U$11") (pin "P$34") (pinfunction "REF64_P$34") (pintype "input"))
      (node (ref "U$8") (pin "P$1") (pinfunction "P$1_P$1") (pintype "bidirectional"))
    )
  )
)
